# DG_V3.net
KiCad netlist of a schematic drawn in Altium Designer
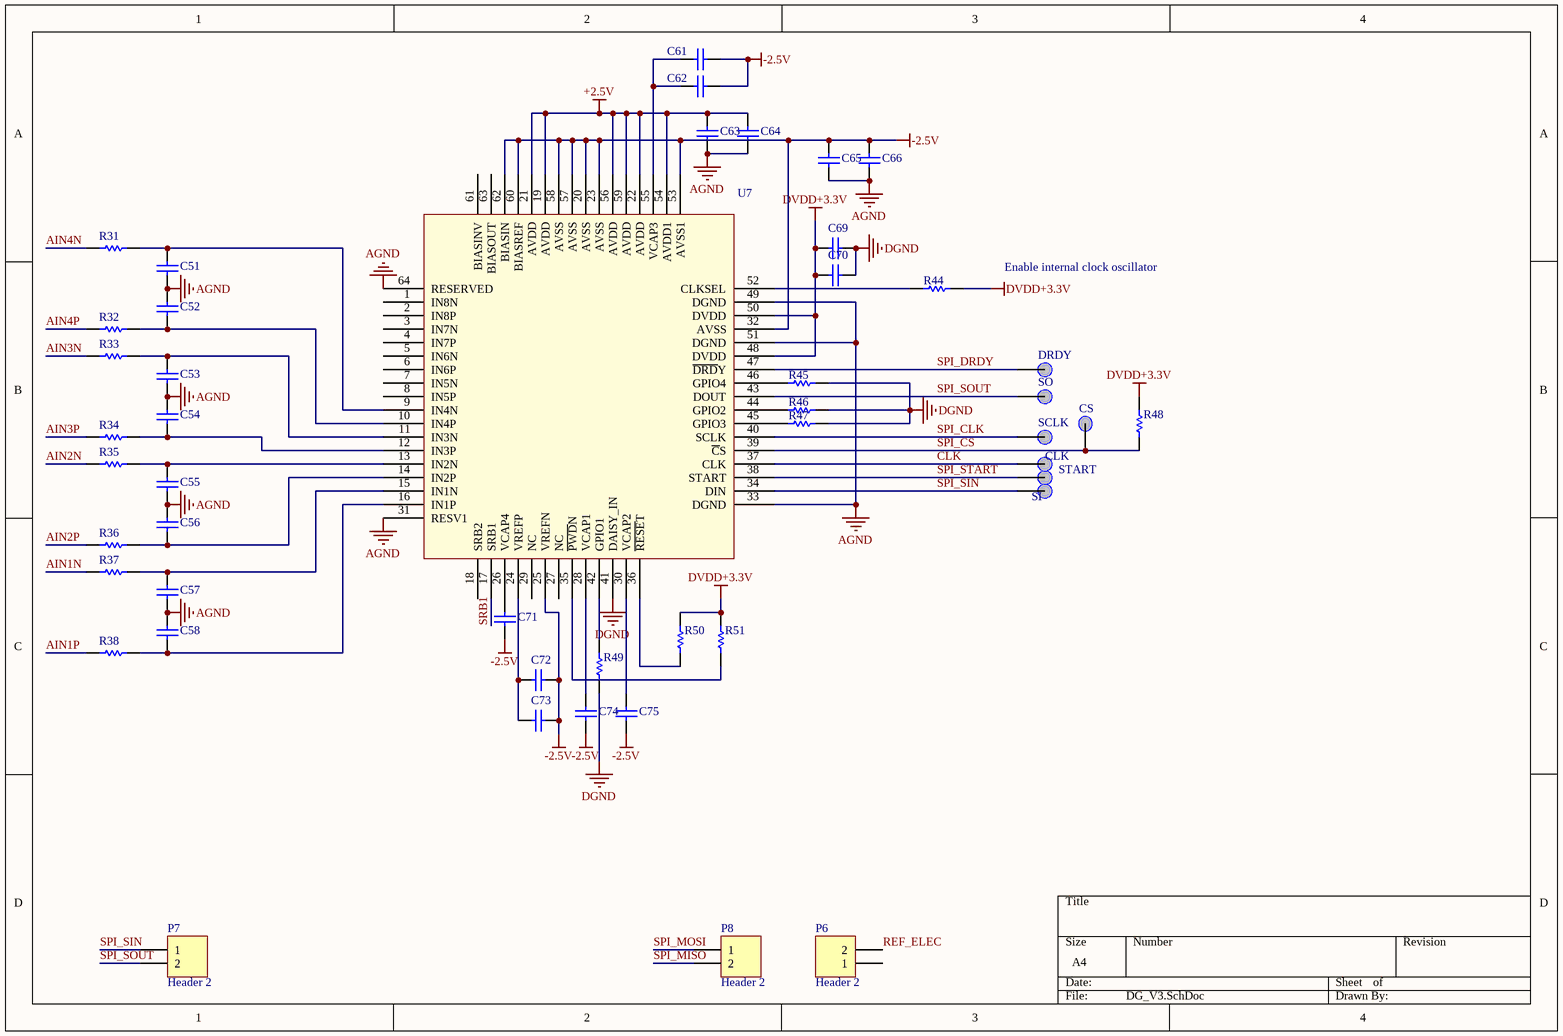
[diagram p0: DG_V3.SchDoc]

(export (version "E")
  (design (tool "Eeschema 10.0.6"))
  (components
    (comp (ref "C51")
      (value "4.7nF")
      (footprint "1608[0603]")
      (description "Capacitor")
      (fields (field (name "PUBLISHER") "Altium Limited"))
      (libsource (lib "Miscellaneous Devices") (part "Cap"))
    )
    (comp (ref "C52")
      (value "4.7nF")
      (footprint "1608[0603]")
      (description "Capacitor")
      (fields (field (name "PUBLISHER") "Altium Limited"))
      (libsource (lib "Miscellaneous Devices") (part "Cap"))
    )
    (comp (ref "C53")
      (value "4.7nF")
      (footprint "1608[0603]")
      (description "Capacitor")
      (fields (field (name "PUBLISHER") "Altium Limited"))
      (libsource (lib "Miscellaneous Devices") (part "Cap"))
    )
    (comp (ref "C54")
      (value "4.7nF")
      (footprint "1608[0603]")
      (description "Capacitor")
      (fields (field (name "PUBLISHER") "Altium Limited"))
      (libsource (lib "Miscellaneous Devices") (part "Cap"))
    )
    (comp (ref "C55")
      (value "4.7nF")
      (footprint "1608[0603]")
      (description "Capacitor")
      (fields (field (name "PUBLISHER") "Altium Limited"))
      (libsource (lib "Miscellaneous Devices") (part "Cap"))
    )
    (comp (ref "C56")
      (value "4.7nF")
      (footprint "1608[0603]")
      (description "Capacitor")
      (fields (field (name "PUBLISHER") "Altium Limited"))
      (libsource (lib "Miscellaneous Devices") (part "Cap"))
    )
    (comp (ref "C57")
      (value "4.7nF")
      (footprint "1608[0603]")
      (description "Capacitor")
      (fields (field (name "PUBLISHER") "Altium Limited"))
      (libsource (lib "Miscellaneous Devices") (part "Cap"))
    )
    (comp (ref "C58")
      (value "4.7nF")
      (footprint "1608[0603]")
      (description "Capacitor")
      (fields (field (name "PUBLISHER") "Altium Limited"))
      (libsource (lib "Miscellaneous Devices") (part "Cap"))
    )
    (comp (ref "C61")
      (value "100nF")
      (footprint "1608[0603]")
      (description "Capacitor")
      (fields (field (name "PUBLISHER") "Altium Limited"))
      (libsource (lib "Miscellaneous Devices") (part "Cap"))
    )
    (comp (ref "C62")
      (value "1uF")
      (footprint "1608[0603]")
      (description "Capacitor")
      (fields (field (name "PUBLISHER") "Altium Limited"))
      (libsource (lib "Miscellaneous Devices") (part "Cap"))
    )
    (comp (ref "C63")
      (value "1uF")
      (footprint "1608[0603]")
      (description "Capacitor")
      (fields (field (name "PUBLISHER") "Altium Limited"))
      (libsource (lib "Miscellaneous Devices") (part "Cap"))
    )
    (comp (ref "C64")
      (value "0.1uF")
      (footprint "1608[0603]")
      (description "Capacitor")
      (fields (field (name "PUBLISHER") "Altium Limited"))
      (libsource (lib "Miscellaneous Devices") (part "Cap"))
    )
    (comp (ref "C65")
      (value "1uF")
      (footprint "1608[0603]")
      (description "Capacitor")
      (fields (field (name "PUBLISHER") "Altium Limited"))
      (libsource (lib "Miscellaneous Devices") (part "Cap"))
    )
    (comp (ref "C66")
      (value "0.1uF")
      (footprint "1608[0603]")
      (description "Capacitor")
      (fields (field (name "PUBLISHER") "Altium Limited"))
      (libsource (lib "Miscellaneous Devices") (part "Cap"))
    )
    (comp (ref "C69")
      (value "1uF")
      (footprint "1608[0603]")
      (description "Capacitor")
      (fields (field (name "PUBLISHER") "Altium Limited"))
      (libsource (lib "Miscellaneous Devices") (part "Cap"))
    )
    (comp (ref "C70")
      (value "0.1uF")
      (footprint "1608[0603]")
      (description "Capacitor")
      (fields (field (name "PUBLISHER") "Altium Limited"))
      (libsource (lib "Miscellaneous Devices") (part "Cap"))
    )
    (comp (ref "C71")
      (value "1uF")
      (footprint "1608[0603]")
      (description "Capacitor")
      (fields (field (name "PUBLISHER") "Altium Limited"))
      (libsource (lib "Miscellaneous Devices") (part "Cap"))
    )
    (comp (ref "C72")
      (value "10uF")
      (footprint "1608[0603]")
      (description "Capacitor")
      (fields (field (name "PUBLISHER") "Altium Limited"))
      (libsource (lib "Miscellaneous Devices") (part "Cap"))
    )
    (comp (ref "C73")
      (value "100nF")
      (footprint "1608[0603]")
      (description "Capacitor")
      (fields (field (name "PUBLISHER") "Altium Limited"))
      (libsource (lib "Miscellaneous Devices") (part "Cap"))
    )
    (comp (ref "C74")
      (value "100uF")
      (footprint "1608[0603]")
      (description "Capacitor")
      (fields (field (name "PUBLISHER") "Altium Limited"))
      (libsource (lib "Miscellaneous Devices") (part "Cap"))
    )
    (comp (ref "C75")
      (value "1uF")
      (footprint "1608[0603]")
      (description "Capacitor")
      (fields (field (name "PUBLISHER") "Altium Limited"))
      (libsource (lib "Miscellaneous Devices") (part "Cap"))
    )
    (comp (ref "CLK") (value "TP") (footprint "TestPort") (libsource (lib "CTs_FYF") (part "TestPoint")))
    (comp (ref "CS") (value "TP") (footprint "TestPort") (libsource (lib "") (part "TestPoint_1")))
    (comp (ref "DRDY") (value "TP") (footprint "TestPort") (libsource (lib "CTs_FYF") (part "TestPoint")))
    (comp (ref "P6")
      (value "Header 2")
      (footprint "HDR1X2")
      (description "Header, 2-Pin")
      (fields (field (name "PUBLISHER") "Altium Limited"))
      (libsource (lib "") (part "Header 2_1"))
    )
    (comp (ref "P7")
      (value "Header 2")
      (footprint "HDR1X2")
      (description "Header, 2-Pin")
      (fields (field (name "PUBLISHER") "Altium Limited"))
      (libsource (lib "Miscellaneous Connectors") (part "Header 2"))
    )
    (comp (ref "P8")
      (value "Header 2")
      (footprint "HDR1X2")
      (description "Header, 2-Pin")
      (fields (field (name "PUBLISHER") "Altium Limited"))
      (libsource (lib "Miscellaneous Connectors") (part "Header 2"))
    )
    (comp (ref "R31")
      (value "4.99K")
      (footprint "J1-0603")
      (description "Resistor")
      (fields (field (name "PUBLISHER") "Altium Limited"))
      (libsource (lib "Miscellaneous Devices") (part "Res1"))
    )
    (comp (ref "R32")
      (value "4.99K")
      (footprint "J1-0603")
      (description "Resistor")
      (fields (field (name "PUBLISHER") "Altium Limited"))
      (libsource (lib "Miscellaneous Devices") (part "Res1"))
    )
    (comp (ref "R33")
      (value "4.99K")
      (footprint "J1-0603")
      (description "Resistor")
      (fields (field (name "PUBLISHER") "Altium Limited"))
      (libsource (lib "Miscellaneous Devices") (part "Res1"))
    )
    (comp (ref "R34")
      (value "4.99K")
      (footprint "J1-0603")
      (description "Resistor")
      (fields (field (name "PUBLISHER") "Altium Limited"))
      (libsource (lib "Miscellaneous Devices") (part "Res1"))
    )
    (comp (ref "R35")
      (value "4.99K")
      (footprint "J1-0603")
      (description "Resistor")
      (fields (field (name "PUBLISHER") "Altium Limited"))
      (libsource (lib "Miscellaneous Devices") (part "Res1"))
    )
    (comp (ref "R36")
      (value "4.99K")
      (footprint "J1-0603")
      (description "Resistor")
      (fields (field (name "PUBLISHER") "Altium Limited"))
      (libsource (lib "Miscellaneous Devices") (part "Res1"))
    )
    (comp (ref "R37")
      (value "4.99K")
      (footprint "J1-0603")
      (description "Resistor")
      (fields (field (name "PUBLISHER") "Altium Limited"))
      (libsource (lib "Miscellaneous Devices") (part "Res1"))
    )
    (comp (ref "R38")
      (value "4.99K")
      (footprint "J1-0603")
      (description "Resistor")
      (fields (field (name "PUBLISHER") "Altium Limited"))
      (libsource (lib "Miscellaneous Devices") (part "Res1"))
    )
    (comp (ref "R44")
      (value "10K")
      (footprint "J1-0603")
      (description "Resistor")
      (fields (field (name "PUBLISHER") "Altium Limited"))
      (libsource (lib "Miscellaneous Devices") (part "Res1"))
    )
    (comp (ref "R45")
      (value "10K")
      (footprint "J1-0603")
      (description "Resistor")
      (fields (field (name "PUBLISHER") "Altium Limited"))
      (libsource (lib "Miscellaneous Devices") (part "Res1"))
    )
    (comp (ref "R46")
      (value "10K")
      (footprint "J1-0603")
      (description "Resistor")
      (fields (field (name "PUBLISHER") "Altium Limited"))
      (libsource (lib "Miscellaneous Devices") (part "Res1"))
    )
    (comp (ref "R47")
      (value "10K")
      (footprint "J1-0603")
      (description "Resistor")
      (fields (field (name "PUBLISHER") "Altium Limited"))
      (libsource (lib "Miscellaneous Devices") (part "Res1"))
    )
    (comp (ref "R48")
      (value "10K")
      (footprint "J1-0603")
      (description "Resistor")
      (fields (field (name "PUBLISHER") "Altium Limited"))
      (libsource (lib "Miscellaneous Devices") (part "Res1"))
    )
    (comp (ref "R49")
      (value "10K")
      (footprint "J1-0603")
      (description "Resistor")
      (fields (field (name "PUBLISHER") "Altium Limited"))
      (libsource (lib "Miscellaneous Devices") (part "Res1"))
    )
    (comp (ref "R50")
      (value "10K")
      (footprint "J1-0603")
      (description "Resistor")
      (fields (field (name "PUBLISHER") "Altium Limited"))
      (libsource (lib "Miscellaneous Devices") (part "Res1"))
    )
    (comp (ref "R51")
      (value "10K")
      (footprint "J1-0603")
      (description "Resistor")
      (fields (field (name "PUBLISHER") "Altium Limited"))
      (libsource (lib "Miscellaneous Devices") (part "Res1"))
    )
    (comp (ref "SCLK") (value "TP") (footprint "TestPort") (libsource (lib "CTs_FYF") (part "TestPoint")))
    (comp (ref "SI") (value "TP") (footprint "TestPort") (libsource (lib "CTs_FYF") (part "TestPoint")))
    (comp (ref "SO") (value "TP") (footprint "TestPort") (libsource (lib "CTs_FYF") (part "TestPoint")))
    (comp (ref "START") (value "TP") (footprint "TestPort") (libsource (lib "CTs_FYF") (part "TestPoint")))
    (comp (ref "U7") (value "ADS1299") (footprint "PQFP-64N") (libsource (lib "CTs_FYF") (part "ADS1299")))
  )
  (nets
    (net (code "1") (name "+2.5V") (class "Default")
      (node (ref "C63") (pin "2") (pinfunction "2_2") (pintype "passive"))
      (node (ref "C64") (pin "2") (pinfunction "2_2") (pintype "passive"))
      (node (ref "U7") (pin "19") (pinfunction "AVDD_19") (pintype "passive"))
      (node (ref "U7") (pin "21") (pinfunction "AVDD_21") (pintype "passive"))
      (node (ref "U7") (pin "22") (pinfunction "AVDD_22") (pintype "passive"))
      (node (ref "U7") (pin "54") (pinfunction "AVDD1_54") (pintype "passive"))
      (node (ref "U7") (pin "56") (pinfunction "AVDD_56") (pintype "passive"))
      (node (ref "U7") (pin "59") (pinfunction "AVDD_59") (pintype "passive"))
    )
    (net (code "2") (name "-2.5V") (class "Default")
      (node (ref "C61") (pin "1") (pinfunction "1_1") (pintype "passive"))
      (node (ref "C62") (pin "1") (pinfunction "1_1") (pintype "passive"))
      (node (ref "C65") (pin "2") (pinfunction "2_2") (pintype "passive"))
      (node (ref "C66") (pin "2") (pinfunction "2_2") (pintype "passive"))
      (node (ref "C71") (pin "1") (pinfunction "1_1") (pintype "passive"))
      (node (ref "C72") (pin "2") (pinfunction "2_2") (pintype "passive"))
      (node (ref "C73") (pin "2") (pinfunction "2_2") (pintype "passive"))
      (node (ref "C74") (pin "1") (pinfunction "1_1") (pintype "passive"))
      (node (ref "C75") (pin "1") (pinfunction "1_1") (pintype "passive"))
      (node (ref "U7") (pin "20") (pinfunction "AVSS_20") (pintype "passive"))
      (node (ref "U7") (pin "23") (pinfunction "AVSS_23") (pintype "passive"))
      (node (ref "U7") (pin "25") (pinfunction "VREFN_25") (pintype "passive"))
      (node (ref "U7") (pin "32") (pinfunction "AVSS_32") (pintype "passive"))
      (node (ref "U7") (pin "53") (pinfunction "AVSS1_53") (pintype "passive"))
      (node (ref "U7") (pin "57") (pinfunction "AVSS_57") (pintype "passive"))
      (node (ref "U7") (pin "58") (pinfunction "AVSS_58") (pintype "passive"))
      (node (ref "U7") (pin "60") (pinfunction "BIASREF_60") (pintype "passive"))
      (node (ref "U7") (pin "62") (pinfunction "BIASIN_62") (pintype "passive"))
    )
    (net (code "3") (name "/AIN1N") (class "Default")
      (node (ref "R37") (pin "1") (pinfunction "1_1") (pintype "passive"))
    )
    (net (code "4") (name "/AIN1P") (class "Default")
      (node (ref "R38") (pin "1") (pinfunction "1_1") (pintype "passive"))
    )
    (net (code "5") (name "/AIN2N") (class "Default")
      (node (ref "R35") (pin "1") (pinfunction "1_1") (pintype "passive"))
    )
    (net (code "6") (name "/AIN2P") (class "Default")
      (node (ref "R36") (pin "1") (pinfunction "1_1") (pintype "passive"))
    )
    (net (code "7") (name "/AIN3N") (class "Default")
      (node (ref "R33") (pin "1") (pinfunction "1_1") (pintype "passive"))
    )
    (net (code "8") (name "/AIN3P") (class "Default")
      (node (ref "R34") (pin "1") (pinfunction "1_1") (pintype "passive"))
    )
    (net (code "9") (name "/AIN4N") (class "Default")
      (node (ref "R31") (pin "1") (pinfunction "1_1") (pintype "passive"))
    )
    (net (code "10") (name "/AIN4P") (class "Default")
      (node (ref "R32") (pin "1") (pinfunction "1_1") (pintype "passive"))
    )
    (net (code "11") (name "/CLK") (class "Default")
      (node (ref "CLK") (pin "0") (pinfunction "0_0") (pintype "passive"))
      (node (ref "U7") (pin "37") (pinfunction "CLK_37") (pintype "passive"))
    )
    (net (code "12") (name "/REF_ELEC") (class "Default")
      (node (ref "P6") (pin "2") (pinfunction "2_2") (pintype "passive"))
    )
    (net (code "13") (name "/SPI_CLK") (class "Default")
      (node (ref "SCLK") (pin "0") (pinfunction "0_0") (pintype "passive"))
      (node (ref "U7") (pin "40") (pinfunction "SCLK_40") (pintype "passive"))
    )
    (net (code "14") (name "/SPI_CS") (class "Default")
      (node (ref "CS") (pin "0") (pinfunction "0_0") (pintype "passive"))
      (node (ref "R48") (pin "2") (pinfunction "2_2") (pintype "passive"))
      (node (ref "U7") (pin "39") (pinfunction "~{C}S_39") (pintype "passive"))
    )
    (net (code "15") (name "/SPI_DRDY") (class "Default")
      (node (ref "DRDY") (pin "0") (pinfunction "0_0") (pintype "passive"))
      (node (ref "U7") (pin "47") (pinfunction "~{DRD}Y_47") (pintype "passive"))
    )
    (net (code "16") (name "/SPI_MISO") (class "Default")
      (node (ref "P8") (pin "2") (pinfunction "2_2") (pintype "passive"))
    )
    (net (code "17") (name "/SPI_MOSI") (class "Default")
      (node (ref "P8") (pin "1") (pinfunction "1_1") (pintype "passive"))
    )
    (net (code "18") (name "/SPI_SIN") (class "Default")
      (node (ref "P7") (pin "1") (pinfunction "1_1") (pintype "passive"))
      (node (ref "SI") (pin "0") (pinfunction "0_0") (pintype "passive"))
      (node (ref "U7") (pin "34") (pinfunction "DIN_34") (pintype "passive"))
    )
    (net (code "19") (name "/SPI_SOUT") (class "Default")
      (node (ref "P7") (pin "2") (pinfunction "2_2") (pintype "passive"))
      (node (ref "SO") (pin "0") (pinfunction "0_0") (pintype "passive"))
      (node (ref "U7") (pin "43") (pinfunction "DOUT_43") (pintype "passive"))
    )
    (net (code "20") (name "/SPI_START") (class "Default")
      (node (ref "START") (pin "0") (pinfunction "0_0") (pintype "passive"))
      (node (ref "U7") (pin "38") (pinfunction "START_38") (pintype "passive"))
    )
    (net (code "21") (name "/SRB1") (class "Default")
      (node (ref "U7") (pin "17") (pinfunction "SRB1_17") (pintype "passive"))
    )
    (net (code "22") (name "AGND") (class "Default")
      (node (ref "C51") (pin "1") (pinfunction "1_1") (pintype "passive"))
      (node (ref "C52") (pin "2") (pinfunction "2_2") (pintype "passive"))
      (node (ref "C53") (pin "1") (pinfunction "1_1") (pintype "passive"))
      (node (ref "C54") (pin "2") (pinfunction "2_2") (pintype "passive"))
      (node (ref "C55") (pin "1") (pinfunction "1_1") (pintype "passive"))
      (node (ref "C56") (pin "2") (pinfunction "2_2") (pintype "passive"))
      (node (ref "C57") (pin "1") (pinfunction "1_1") (pintype "passive"))
      (node (ref "C58") (pin "2") (pinfunction "2_2") (pintype "passive"))
      (node (ref "C63") (pin "1") (pinfunction "1_1") (pintype "passive"))
      (node (ref "C64") (pin "1") (pinfunction "1_1") (pintype "passive"))
      (node (ref "C65") (pin "1") (pinfunction "1_1") (pintype "passive"))
      (node (ref "C66") (pin "1") (pinfunction "1_1") (pintype "passive"))
      (node (ref "U7") (pin "31") (pinfunction "RESV1_31") (pintype "passive"))
      (node (ref "U7") (pin "33") (pinfunction "DGND_33") (pintype "passive"))
      (node (ref "U7") (pin "49") (pinfunction "DGND_49") (pintype "passive"))
      (node (ref "U7") (pin "51") (pinfunction "DGND_51") (pintype "passive"))
      (node (ref "U7") (pin "64") (pinfunction "RESERVED_64") (pintype "passive"))
    )
    (net (code "23") (name "DGND") (class "Default")
      (node (ref "C69") (pin "1") (pinfunction "1_1") (pintype "passive"))
      (node (ref "C70") (pin "1") (pinfunction "1_1") (pintype "passive"))
      (node (ref "R45") (pin "1") (pinfunction "1_1") (pintype "passive"))
      (node (ref "R46") (pin "1") (pinfunction "1_1") (pintype "passive"))
      (node (ref "R47") (pin "1") (pinfunction "1_1") (pintype "passive"))
      (node (ref "R49") (pin "1") (pinfunction "1_1") (pintype "passive"))
      (node (ref "U7") (pin "41") (pinfunction "DAISY_IN_41") (pintype "passive"))
    )
    (net (code "24") (name "DVDD+3.3V") (class "Default")
      (node (ref "C69") (pin "2") (pinfunction "2_2") (pintype "passive"))
      (node (ref "C70") (pin "2") (pinfunction "2_2") (pintype "passive"))
      (node (ref "R44") (pin "1") (pinfunction "1_1") (pintype "passive"))
      (node (ref "R48") (pin "1") (pinfunction "1_1") (pintype "passive"))
      (node (ref "R50") (pin "1") (pinfunction "1_1") (pintype "passive"))
      (node (ref "R51") (pin "1") (pinfunction "1_1") (pintype "passive"))
      (node (ref "U7") (pin "48") (pinfunction "DVDD_48") (pintype "passive"))
      (node (ref "U7") (pin "50") (pinfunction "DVDD_50") (pintype "passive"))
    )
    (net (code "25") (name "Net-(U7-CLKSEL)") (class "Default")
      (node (ref "R44") (pin "2") (pinfunction "2_2") (pintype "passive"))
      (node (ref "U7") (pin "52") (pinfunction "CLKSEL_52") (pintype "passive"))
    )
    (net (code "26") (name "Net-(U7-GPIO1)") (class "Default")
      (node (ref "R49") (pin "2") (pinfunction "2_2") (pintype "passive"))
      (node (ref "U7") (pin "42") (pinfunction "GPIO1_42") (pintype "passive"))
    )
    (net (code "27") (name "Net-(U7-GPIO2)") (class "Default")
      (node (ref "R46") (pin "2") (pinfunction "2_2") (pintype "passive"))
      (node (ref "U7") (pin "44") (pinfunction "GPIO2_44") (pintype "passive"))
    )
    (net (code "28") (name "Net-(U7-GPIO3)") (class "Default")
      (node (ref "R47") (pin "2") (pinfunction "2_2") (pintype "passive"))
      (node (ref "U7") (pin "45") (pinfunction "GPIO3_45") (pintype "passive"))
    )
    (net (code "29") (name "Net-(U7-GPIO4)") (class "Default")
      (node (ref "R45") (pin "2") (pinfunction "2_2") (pintype "passive"))
      (node (ref "U7") (pin "46") (pinfunction "GPIO4_46") (pintype "passive"))
    )
    (net (code "30") (name "Net-(U7-IN1N)") (class "Default")
      (node (ref "C57") (pin "2") (pinfunction "2_2") (pintype "passive"))
      (node (ref "R37") (pin "2") (pinfunction "2_2") (pintype "passive"))
      (node (ref "U7") (pin "15") (pinfunction "IN1N_15") (pintype "passive"))
    )
    (net (code "31") (name "Net-(U7-IN1P)") (class "Default")
      (node (ref "C58") (pin "1") (pinfunction "1_1") (pintype "passive"))
      (node (ref "R38") (pin "2") (pinfunction "2_2") (pintype "passive"))
      (node (ref "U7") (pin "16") (pinfunction "IN1P_16") (pintype "passive"))
    )
    (net (code "32") (name "Net-(U7-IN2N)") (class "Default")
      (node (ref "C55") (pin "2") (pinfunction "2_2") (pintype "passive"))
      (node (ref "R35") (pin "2") (pinfunction "2_2") (pintype "passive"))
      (node (ref "U7") (pin "13") (pinfunction "IN2N_13") (pintype "passive"))
    )
    (net (code "33") (name "Net-(U7-IN2P)") (class "Default")
      (node (ref "C56") (pin "1") (pinfunction "1_1") (pintype "passive"))
      (node (ref "R36") (pin "2") (pinfunction "2_2") (pintype "passive"))
      (node (ref "U7") (pin "14") (pinfunction "IN2P_14") (pintype "passive"))
    )
    (net (code "34") (name "Net-(U7-IN3N)") (class "Default")
      (node (ref "C53") (pin "2") (pinfunction "2_2") (pintype "passive"))
      (node (ref "R33") (pin "2") (pinfunction "2_2") (pintype "passive"))
      (node (ref "U7") (pin "11") (pinfunction "IN3N_11") (pintype "passive"))
    )
    (net (code "35") (name "Net-(U7-IN3P)") (class "Default")
      (node (ref "C54") (pin "1") (pinfunction "1_1") (pintype "passive"))
      (node (ref "R34") (pin "2") (pinfunction "2_2") (pintype "passive"))
      (node (ref "U7") (pin "12") (pinfunction "IN3P_12") (pintype "passive"))
    )
    (net (code "36") (name "Net-(U7-IN4N)") (class "Default")
      (node (ref "C51") (pin "2") (pinfunction "2_2") (pintype "passive"))
      (node (ref "R31") (pin "2") (pinfunction "2_2") (pintype "passive"))
      (node (ref "U7") (pin "9") (pinfunction "IN4N_9") (pintype "passive"))
    )
    (net (code "37") (name "Net-(U7-IN4P)") (class "Default")
      (node (ref "C52") (pin "1") (pinfunction "1_1") (pintype "passive"))
      (node (ref "R32") (pin "2") (pinfunction "2_2") (pintype "passive"))
      (node (ref "U7") (pin "10") (pinfunction "IN4P_10") (pintype "passive"))
    )
    (net (code "38") (name "Net-(U7-VCAP1)") (class "Default")
      (node (ref "C74") (pin "2") (pinfunction "2_2") (pintype "passive"))
      (node (ref "U7") (pin "28") (pinfunction "VCAP1_28") (pintype "passive"))
    )
    (net (code "39") (name "Net-(U7-VCAP2)") (class "Default")
      (node (ref "C75") (pin "2") (pinfunction "2_2") (pintype "passive"))
      (node (ref "U7") (pin "30") (pinfunction "VCAP2_30") (pintype "passive"))
    )
    (net (code "40") (name "Net-(U7-VCAP3)") (class "Default")
      (node (ref "C61") (pin "2") (pinfunction "2_2") (pintype "passive"))
      (node (ref "C62") (pin "2") (pinfunction "2_2") (pintype "passive"))
      (node (ref "U7") (pin "55") (pinfunction "VCAP3_55") (pintype "passive"))
    )
    (net (code "41") (name "Net-(U7-VCAP4)") (class "Default")
      (node (ref "C71") (pin "2") (pinfunction "2_2") (pintype "passive"))
      (node (ref "U7") (pin "26") (pinfunction "VCAP4_26") (pintype "passive"))
    )
    (net (code "42") (name "Net-(U7-VREFP)") (class "Default")
      (node (ref "C72") (pin "1") (pinfunction "1_1") (pintype "passive"))
      (node (ref "C73") (pin "1") (pinfunction "1_1") (pintype "passive"))
      (node (ref "U7") (pin "24") (pinfunction "VREFP_24") (pintype "passive"))
    )
    (net (code "43") (name "Net-(U7-~{PWD}N)") (class "Default")
      (node (ref "R51") (pin "2") (pinfunction "2_2") (pintype "passive"))
      (node (ref "U7") (pin "35") (pinfunction "~{PWD}N_35") (pintype "passive"))
    )
    (net (code "44") (name "Net-(U7-~{RESE}T)") (class "Default")
      (node (ref "R50") (pin "2") (pinfunction "2_2") (pintype "passive"))
      (node (ref "U7") (pin "36") (pinfunction "~{RESE}T_36") (pintype "passive"))
    )
    (net (code "45") (name "unconnected-(P6-Pad1)") (class "Default")
      (node (ref "P6") (pin "1") (pinfunction "1_1") (pintype "passive"))
    )
    (net (code "46") (name "unconnected-(U7-BIASINV-Pad61)") (class "Default")
      (node (ref "U7") (pin "61") (pinfunction "BIASINV_61") (pintype "passive"))
    )
    (net (code "47") (name "unconnected-(U7-BIASOUT-Pad63)") (class "Default")
      (node (ref "U7") (pin "63") (pinfunction "BIASOUT_63") (pintype "passive"))
    )
    (net (code "48") (name "unconnected-(U7-IN5N-Pad7)") (class "Default")
      (node (ref "U7") (pin "7") (pinfunction "IN5N_7") (pintype "passive"))
    )
    (net (code "49") (name "unconnected-(U7-IN5P-Pad8)") (class "Default")
      (node (ref "U7") (pin "8") (pinfunction "IN5P_8") (pintype "passive"))
    )
    (net (code "50") (name "unconnected-(U7-IN6N-Pad5)") (class "Default")
      (node (ref "U7") (pin "5") (pinfunction "IN6N_5") (pintype "passive"))
    )
    (net (code "51") (name "unconnected-(U7-IN6P-Pad6)") (class "Default")
      (node (ref "U7") (pin "6") (pinfunction "IN6P_6") (pintype "passive"))
    )
    (net (code "52") (name "unconnected-(U7-IN7N-Pad3)") (class "Default")
      (node (ref "U7") (pin "3") (pinfunction "IN7N_3") (pintype "passive"))
    )
    (net (code "53") (name "unconnected-(U7-IN7P-Pad4)") (class "Default")
      (node (ref "U7") (pin "4") (pinfunction "IN7P_4") (pintype "passive"))
    )
    (net (code "54") (name "unconnected-(U7-IN8N-Pad1)") (class "Default")
      (node (ref "U7") (pin "1") (pinfunction "IN8N_1") (pintype "passive"))
    )
    (net (code "55") (name "unconnected-(U7-IN8P-Pad2)") (class "Default")
      (node (ref "U7") (pin "2") (pinfunction "IN8P_2") (pintype "passive"))
    )
    (net (code "56") (name "unconnected-(U7-NC-Pad27)") (class "Default")
      (node (ref "U7") (pin "27") (pinfunction "NC_27") (pintype "passive"))
    )
    (net (code "57") (name "unconnected-(U7-NC-Pad29)") (class "Default")
      (node (ref "U7") (pin "29") (pinfunction "NC_29") (pintype "passive"))
    )
    (net (code "58") (name "unconnected-(U7-SRB2-Pad18)") (class "Default")
      (node (ref "U7") (pin "18") (pinfunction "SRB2_18") (pintype "passive"))
    )
  )
)
